# USB_A_Filter.net
KiCad netlist of a schematic drawn in Altium Designer
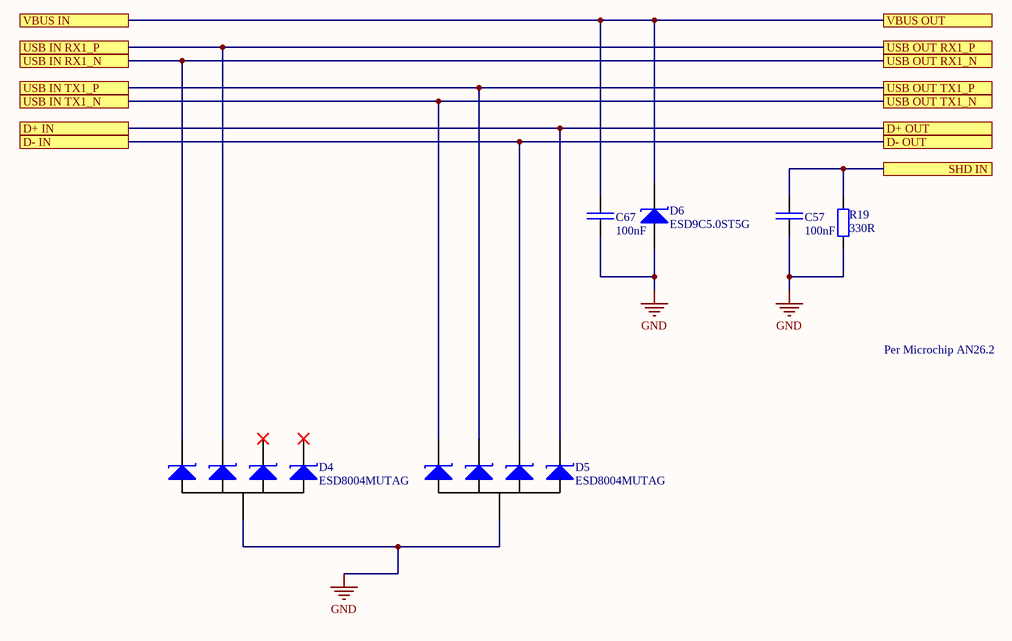
[diagram p0: USB A Filter.SchDoc]

(export (version "E")
  (design (tool "Eeschema 10.0.6"))
  (components
    (comp (ref "C57")
      (value "100nF")
      (footprint "CAP_SM0603_YAGEOCC2_N")
      (description "CAP 100nF SM0603 X7R 50V YAGEO CC2")
      (fields
        (field (name "MANUFACTURER") "Yageo")
        (field (name "MANUFACTURER PART NUMBER") "CC0603KRX7R9BB104")
      )
      (libsource (lib "Yageo") (part "CC0603KRX7R9BB104"))
    )
    (comp (ref "C67")
      (value "100nF")
      (footprint "CAP_SM0603_YAGEOCC2_N")
      (description "CAP 100nF SM0603 X7R 50V YAGEO CC2")
      (fields
        (field (name "MANUFACTURER") "Yageo")
        (field (name "MANUFACTURER PART NUMBER") "CC0603KRX7R9BB104")
      )
      (libsource (lib "Yageo") (part "CC0603KRX7R9BB104"))
    )
    (comp (ref "D4")
      (value "ESD8004MUTAG")
      (footprint "ESD8004MUTAG")
      (description "TVS DIODE 3.3VWM 8VC 10UDFN")
      (libsource (lib "KBuchka-IntLib") (part "ESD8004MUTAG"))
    )
    (comp (ref "D5")
      (value "ESD8004MUTAG")
      (footprint "ESD8004MUTAG")
      (description "TVS DIODE 3.3VWM 8VC 10UDFN")
      (libsource (lib "KBuchka-IntLib") (part "ESD8004MUTAG"))
    )
    (comp (ref "D6")
      (value "ESD9C5.0ST5G")
      (footprint "SODFL100X40-2N - ESD9C5.0ST5G")
      (description "TVS DIODE 5VWM SOD923")
      (libsource (lib "KBuchka-IntLib") (part "ESD9C5.0ST5G"))
    )
    (comp (ref "R19")
      (value "330R")
      (footprint "RES_SM0603_YAGEORC_N")
      (description "RES 330R SM0603 YAGEO RC_L")
      (fields
        (field (name "MANUFACTURER") "Yageo")
        (field (name "MANUFACTURER PART NUMBER") "RC0603FR-07330RL")
      )
      (libsource (lib "Yageo") (part "RC0603FR-07330RL"))
    )
  )
  (nets
    (net (code "1") (name "/D+ IN") (class "Default")
      (node (ref "D5") (pin "5") (pinfunction "K_5") (pintype "passive"))
    )
    (net (code "2") (name "/D- IN") (class "Default")
      (node (ref "D5") (pin "4") (pinfunction "K_4") (pintype "passive"))
    )
    (net (code "3") (name "/SHD IN") (class "Default")
      (node (ref "C57") (pin "1") (pintype "passive"))
      (node (ref "R19") (pin "2") (pintype "passive"))
    )
    (net (code "4") (name "/USB IN RX1_N") (class "Default")
      (node (ref "D4") (pin "1") (pinfunction "K_1") (pintype "passive"))
    )
    (net (code "5") (name "/USB IN RX1_P") (class "Default")
      (node (ref "D4") (pin "2") (pinfunction "K_2") (pintype "passive"))
    )
    (net (code "6") (name "/USB IN TX1_N") (class "Default")
      (node (ref "D5") (pin "1") (pinfunction "K_1") (pintype "passive"))
    )
    (net (code "7") (name "/USB IN TX1_P") (class "Default")
      (node (ref "D5") (pin "2") (pinfunction "K_2") (pintype "passive"))
    )
    (net (code "8") (name "/VBUS IN") (class "Default")
      (node (ref "C67") (pin "1") (pintype "passive"))
      (node (ref "D6") (pin "1") (pinfunction "K_1") (pintype "passive"))
    )
    (net (code "9") (name "GND") (class "Default")
      (node (ref "C57") (pin "2") (pintype "passive"))
      (node (ref "C67") (pin "2") (pintype "passive"))
      (node (ref "D4") (pin "GND") (pinfunction "A_GND") (pintype "passive"))
      (node (ref "D5") (pin "GND") (pinfunction "A_GND") (pintype "passive"))
      (node (ref "D6") (pin "2") (pinfunction "2_2") (pintype "passive"))
      (node (ref "R19") (pin "1") (pintype "passive"))
    )
    (net (code "10") (name "unconnected-(D4-K-Pad4)") (class "Default")
      (node (ref "D4") (pin "4") (pinfunction "K_4") (pintype "passive+no_connect"))
    )
    (net (code "11") (name "unconnected-(D4-K-Pad5)") (class "Default")
      (node (ref "D4") (pin "5") (pinfunction "K_5") (pintype "passive+no_connect"))
    )
  )
)
